# mechanical.net
KiCad netlist of a schematic drawn in Altium Designer
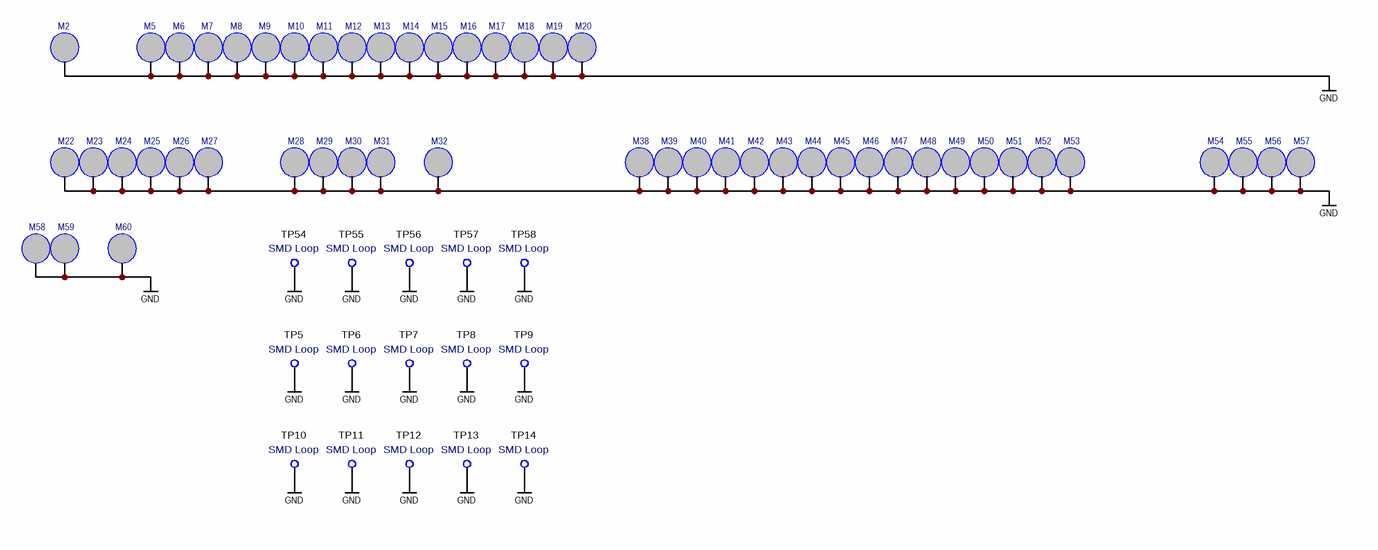
[diagram p0: mechanical.SchDoc]

(export (version "E")
  (design (tool "Eeschema 10.0.6"))
  (components
    (comp (ref "M2") (value "MOUNT") (footprint "MOUNTM3") (libsource (lib "generic") (part "MOUNT")))
    (comp (ref "M5") (value "MOUNT") (footprint "MOUNTM3") (libsource (lib "generic") (part "MOUNT")))
    (comp (ref "M6") (value "MOUNT") (footprint "MOUNTM3") (libsource (lib "generic") (part "MOUNT")))
    (comp (ref "M7") (value "MOUNT") (footprint "MOUNTM3") (libsource (lib "generic") (part "MOUNT")))
    (comp (ref "M8") (value "MOUNT") (footprint "MOUNTM3") (libsource (lib "generic") (part "MOUNT")))
    (comp (ref "M9") (value "MOUNT") (footprint "MOUNTM3") (libsource (lib "generic") (part "MOUNT")))
    (comp (ref "M10") (value "MOUNT") (footprint "MOUNTM3") (libsource (lib "generic") (part "MOUNT")))
    (comp (ref "M11") (value "MOUNT") (footprint "MOUNTM3") (libsource (lib "generic") (part "MOUNT")))
    (comp (ref "M12") (value "MOUNT") (footprint "MOUNTM3") (libsource (lib "generic") (part "MOUNT")))
    (comp (ref "M13") (value "MOUNT") (footprint "MOUNTM3") (libsource (lib "generic") (part "MOUNT")))
    (comp (ref "M14") (value "MOUNT") (footprint "MOUNTM3") (libsource (lib "generic") (part "MOUNT")))
    (comp (ref "M15") (value "MOUNT") (footprint "MOUNTM3") (libsource (lib "generic") (part "MOUNT")))
    (comp (ref "M16") (value "MOUNT") (footprint "MOUNTM3") (libsource (lib "generic") (part "MOUNT")))
    (comp (ref "M17") (value "MOUNT") (footprint "MOUNTM3") (libsource (lib "generic") (part "MOUNT")))
    (comp (ref "M18") (value "MOUNT") (footprint "MOUNTM3") (libsource (lib "generic") (part "MOUNT")))
    (comp (ref "M19") (value "MOUNT") (footprint "MOUNTM3") (libsource (lib "generic") (part "MOUNT")))
    (comp (ref "M20") (value "MOUNT") (footprint "MOUNTM3") (libsource (lib "generic") (part "MOUNT")))
    (comp (ref "M22") (value "MOUNT") (footprint "MOUNTM3") (libsource (lib "generic") (part "MOUNT")))
    (comp (ref "M23") (value "MOUNT") (footprint "MOUNTM3") (libsource (lib "generic") (part "MOUNT")))
    (comp (ref "M24") (value "MOUNT") (footprint "MOUNTM3") (libsource (lib "generic") (part "MOUNT")))
    (comp (ref "M25") (value "MOUNT") (footprint "MOUNTM3") (libsource (lib "generic") (part "MOUNT")))
    (comp (ref "M26") (value "MOUNT") (footprint "MOUNTM3") (libsource (lib "generic") (part "MOUNT")))
    (comp (ref "M27") (value "MOUNT") (footprint "MOUNTM3") (libsource (lib "generic") (part "MOUNT")))
    (comp (ref "M28") (value "MOUNT") (footprint "MOUNTM3") (libsource (lib "generic") (part "MOUNT")))
    (comp (ref "M29") (value "MOUNT") (footprint "MOUNTM3") (libsource (lib "generic") (part "MOUNT")))
    (comp (ref "M30") (value "MOUNT") (footprint "MOUNTM3") (libsource (lib "generic") (part "MOUNT")))
    (comp (ref "M31") (value "MOUNT") (footprint "MOUNTM3") (libsource (lib "generic") (part "MOUNT")))
    (comp (ref "M32") (value "MOUNT") (footprint "MOUNTM3") (libsource (lib "generic") (part "MOUNT")))
    (comp (ref "M38") (value "MOUNT") (footprint "MOUNTM3") (libsource (lib "generic") (part "MOUNT")))
    (comp (ref "M39") (value "MOUNT") (footprint "MOUNTM3") (libsource (lib "generic") (part "MOUNT")))
    (comp (ref "M40") (value "MOUNT") (footprint "MOUNTM3") (libsource (lib "generic") (part "MOUNT")))
    (comp (ref "M41") (value "MOUNT") (footprint "MOUNTM3") (libsource (lib "generic") (part "MOUNT")))
    (comp (ref "M42") (value "MOUNT") (footprint "MOUNTM3") (libsource (lib "generic") (part "MOUNT")))
    (comp (ref "M43") (value "MOUNT") (footprint "MOUNTM3") (libsource (lib "generic") (part "MOUNT")))
    (comp (ref "M44") (value "MOUNT") (footprint "MOUNTM3") (libsource (lib "generic") (part "MOUNT")))
    (comp (ref "M45") (value "MOUNT") (footprint "MOUNTM3") (libsource (lib "generic") (part "MOUNT")))
    (comp (ref "M46") (value "MOUNT") (footprint "MOUNTM3") (libsource (lib "generic") (part "MOUNT")))
    (comp (ref "M47") (value "MOUNT") (footprint "MOUNTM3") (libsource (lib "generic") (part "MOUNT")))
    (comp (ref "M48") (value "MOUNT") (footprint "MOUNTM3") (libsource (lib "generic") (part "MOUNT")))
    (comp (ref "M49") (value "MOUNT") (footprint "MOUNTM3") (libsource (lib "generic") (part "MOUNT")))
    (comp (ref "M50") (value "MOUNT") (footprint "MOUNTM3") (libsource (lib "generic") (part "MOUNT")))
    (comp (ref "M51") (value "MOUNT") (footprint "MOUNTM3") (libsource (lib "generic") (part "MOUNT")))
    (comp (ref "M52") (value "MOUNT") (footprint "MOUNTM3") (libsource (lib "generic") (part "MOUNT")))
    (comp (ref "M53") (value "MOUNT") (footprint "MOUNTM3") (libsource (lib "generic") (part "MOUNT")))
    (comp (ref "M54") (value "MOUNT") (footprint "MOUNTM3") (libsource (lib "generic") (part "MOUNT")))
    (comp (ref "M55") (value "MOUNT") (footprint "MOUNTM3") (libsource (lib "generic") (part "MOUNT")))
    (comp (ref "M56") (value "MOUNT") (footprint "MOUNTM3") (libsource (lib "generic") (part "MOUNT")))
    (comp (ref "M57") (value "MOUNT") (footprint "MOUNTM3") (libsource (lib "generic") (part "MOUNT")))
    (comp (ref "M58") (value "MOUNT") (footprint "MOUNTM3") (libsource (lib "generic") (part "MOUNT")))
    (comp (ref "M59") (value "MOUNT") (footprint "MOUNTM3") (libsource (lib "generic") (part "MOUNT")))
    (comp (ref "M60") (value "MOUNT") (footprint "MOUNTM3") (libsource (lib "generic") (part "MOUNT")))
    (comp (ref "TP5")
      (value "5015")
      (footprint "keystone:5015")
      (description "Test Point SMD")
      (fields (field (name "MANUFACTURER") "Keystone") (field (name "NOTES") "SMD Loop"))
      (libsource (lib "generic") (part "TEST_POINT_SMD_50"))
    )
    (comp (ref "TP6")
      (value "5015")
      (footprint "keystone:5015")
      (description "Test Point SMD")
      (fields (field (name "MANUFACTURER") "Keystone") (field (name "NOTES") "SMD Loop"))
      (libsource (lib "generic") (part "TEST_POINT_SMD_50"))
    )
    (comp (ref "TP7")
      (value "5015")
      (footprint "keystone:5015")
      (description "Test Point SMD")
      (fields (field (name "MANUFACTURER") "Keystone") (field (name "NOTES") "SMD Loop"))
      (libsource (lib "generic") (part "TEST_POINT_SMD_50"))
    )
    (comp (ref "TP8")
      (value "5015")
      (footprint "keystone:5015")
      (description "Test Point SMD")
      (fields (field (name "MANUFACTURER") "Keystone") (field (name "NOTES") "SMD Loop"))
      (libsource (lib "generic") (part "TEST_POINT_SMD_50"))
    )
    (comp (ref "TP9")
      (value "5015")
      (footprint "keystone:5015")
      (description "Test Point SMD")
      (fields (field (name "MANUFACTURER") "Keystone") (field (name "NOTES") "SMD Loop"))
      (libsource (lib "generic") (part "TEST_POINT_SMD_50"))
    )
    (comp (ref "TP10")
      (value "5015")
      (footprint "keystone:5015")
      (description "Test Point SMD")
      (fields (field (name "MANUFACTURER") "Keystone") (field (name "NOTES") "SMD Loop"))
      (libsource (lib "generic") (part "TEST_POINT_SMD_50"))
    )
    (comp (ref "TP11")
      (value "5015")
      (footprint "keystone:5015")
      (description "Test Point SMD")
      (fields (field (name "MANUFACTURER") "Keystone") (field (name "NOTES") "SMD Loop"))
      (libsource (lib "generic") (part "TEST_POINT_SMD_50"))
    )
    (comp (ref "TP12")
      (value "5015")
      (footprint "keystone:5015")
      (description "Test Point SMD")
      (fields (field (name "MANUFACTURER") "Keystone") (field (name "NOTES") "SMD Loop"))
      (libsource (lib "generic") (part "TEST_POINT_SMD_50"))
    )
    (comp (ref "TP13")
      (value "5015")
      (footprint "keystone:5015")
      (description "Test Point SMD")
      (fields (field (name "MANUFACTURER") "Keystone") (field (name "NOTES") "SMD Loop"))
      (libsource (lib "generic") (part "TEST_POINT_SMD_50"))
    )
    (comp (ref "TP14")
      (value "5015")
      (footprint "keystone:5015")
      (description "Test Point SMD")
      (fields (field (name "MANUFACTURER") "Keystone") (field (name "NOTES") "SMD Loop"))
      (libsource (lib "generic") (part "TEST_POINT_SMD_50"))
    )
    (comp (ref "TP54")
      (value "5015")
      (footprint "keystone:5015")
      (description "Test Point SMD")
      (fields (field (name "MANUFACTURER") "Keystone") (field (name "NOTES") "SMD Loop"))
      (libsource (lib "generic") (part "TEST_POINT_SMD_50"))
    )
    (comp (ref "TP55")
      (value "5015")
      (footprint "keystone:5015")
      (description "Test Point SMD")
      (fields (field (name "MANUFACTURER") "Keystone") (field (name "NOTES") "SMD Loop"))
      (libsource (lib "generic") (part "TEST_POINT_SMD_50"))
    )
    (comp (ref "TP56")
      (value "5015")
      (footprint "keystone:5015")
      (description "Test Point SMD")
      (fields (field (name "MANUFACTURER") "Keystone") (field (name "NOTES") "SMD Loop"))
      (libsource (lib "generic") (part "TEST_POINT_SMD_50"))
    )
    (comp (ref "TP57")
      (value "5015")
      (footprint "keystone:5015")
      (description "Test Point SMD")
      (fields (field (name "MANUFACTURER") "Keystone") (field (name "NOTES") "SMD Loop"))
      (libsource (lib "generic") (part "TEST_POINT_SMD_50"))
    )
    (comp (ref "TP58")
      (value "5015")
      (footprint "keystone:5015")
      (description "Test Point SMD")
      (fields (field (name "MANUFACTURER") "Keystone") (field (name "NOTES") "SMD Loop"))
      (libsource (lib "generic") (part "TEST_POINT_SMD_50"))
    )
  )
  (nets
    (net (code "1") (name "GND") (class "Default")
      (node (ref "M10") (pin "1") (pinfunction "MNT_1") (pintype "passive"))
      (node (ref "M11") (pin "1") (pinfunction "MNT_1") (pintype "passive"))
      (node (ref "M12") (pin "1") (pinfunction "MNT_1") (pintype "passive"))
      (node (ref "M13") (pin "1") (pinfunction "MNT_1") (pintype "passive"))
      (node (ref "M14") (pin "1") (pinfunction "MNT_1") (pintype "passive"))
      (node (ref "M15") (pin "1") (pinfunction "MNT_1") (pintype "passive"))
      (node (ref "M16") (pin "1") (pinfunction "MNT_1") (pintype "passive"))
      (node (ref "M17") (pin "1") (pinfunction "MNT_1") (pintype "passive"))
      (node (ref "M18") (pin "1") (pinfunction "MNT_1") (pintype "passive"))
      (node (ref "M19") (pin "1") (pinfunction "MNT_1") (pintype "passive"))
      (node (ref "M2") (pin "1") (pinfunction "MNT_1") (pintype "passive"))
      (node (ref "M20") (pin "1") (pinfunction "MNT_1") (pintype "passive"))
      (node (ref "M22") (pin "1") (pinfunction "MNT_1") (pintype "passive"))
      (node (ref "M23") (pin "1") (pinfunction "MNT_1") (pintype "passive"))
      (node (ref "M24") (pin "1") (pinfunction "MNT_1") (pintype "passive"))
      (node (ref "M25") (pin "1") (pinfunction "MNT_1") (pintype "passive"))
      (node (ref "M26") (pin "1") (pinfunction "MNT_1") (pintype "passive"))
      (node (ref "M27") (pin "1") (pinfunction "MNT_1") (pintype "passive"))
      (node (ref "M28") (pin "1") (pinfunction "MNT_1") (pintype "passive"))
      (node (ref "M29") (pin "1") (pinfunction "MNT_1") (pintype "passive"))
      (node (ref "M30") (pin "1") (pinfunction "MNT_1") (pintype "passive"))
      (node (ref "M31") (pin "1") (pinfunction "MNT_1") (pintype "passive"))
      (node (ref "M32") (pin "1") (pinfunction "MNT_1") (pintype "passive"))
      (node (ref "M38") (pin "1") (pinfunction "MNT_1") (pintype "passive"))
      (node (ref "M39") (pin "1") (pinfunction "MNT_1") (pintype "passive"))
      (node (ref "M40") (pin "1") (pinfunction "MNT_1") (pintype "passive"))
      (node (ref "M41") (pin "1") (pinfunction "MNT_1") (pintype "passive"))
      (node (ref "M42") (pin "1") (pinfunction "MNT_1") (pintype "passive"))
      (node (ref "M43") (pin "1") (pinfunction "MNT_1") (pintype "passive"))
      (node (ref "M44") (pin "1") (pinfunction "MNT_1") (pintype "passive"))
      (node (ref "M45") (pin "1") (pinfunction "MNT_1") (pintype "passive"))
      (node (ref "M46") (pin "1") (pinfunction "MNT_1") (pintype "passive"))
      (node (ref "M47") (pin "1") (pinfunction "MNT_1") (pintype "passive"))
      (node (ref "M48") (pin "1") (pinfunction "MNT_1") (pintype "passive"))
      (node (ref "M49") (pin "1") (pinfunction "MNT_1") (pintype "passive"))
      (node (ref "M5") (pin "1") (pinfunction "MNT_1") (pintype "passive"))
      (node (ref "M50") (pin "1") (pinfunction "MNT_1") (pintype "passive"))
      (node (ref "M51") (pin "1") (pinfunction "MNT_1") (pintype "passive"))
      (node (ref "M52") (pin "1") (pinfunction "MNT_1") (pintype "passive"))
      (node (ref "M53") (pin "1") (pinfunction "MNT_1") (pintype "passive"))
      (node (ref "M54") (pin "1") (pinfunction "MNT_1") (pintype "passive"))
      (node (ref "M55") (pin "1") (pinfunction "MNT_1") (pintype "passive"))
      (node (ref "M56") (pin "1") (pinfunction "MNT_1") (pintype "passive"))
      (node (ref "M57") (pin "1") (pinfunction "MNT_1") (pintype "passive"))
      (node (ref "M58") (pin "1") (pinfunction "MNT_1") (pintype "passive"))
      (node (ref "M59") (pin "1") (pinfunction "MNT_1") (pintype "passive"))
      (node (ref "M6") (pin "1") (pinfunction "MNT_1") (pintype "passive"))
      (node (ref "M60") (pin "1") (pinfunction "MNT_1") (pintype "passive"))
      (node (ref "M7") (pin "1") (pinfunction "MNT_1") (pintype "passive"))
      (node (ref "M8") (pin "1") (pinfunction "MNT_1") (pintype "passive"))
      (node (ref "M9") (pin "1") (pinfunction "MNT_1") (pintype "passive"))
      (node (ref "TP10") (pin "1") (pinfunction "1_1") (pintype "passive"))
      (node (ref "TP11") (pin "1") (pinfunction "1_1") (pintype "passive"))
      (node (ref "TP12") (pin "1") (pinfunction "1_1") (pintype "passive"))
      (node (ref "TP13") (pin "1") (pinfunction "1_1") (pintype "passive"))
      (node (ref "TP14") (pin "1") (pinfunction "1_1") (pintype "passive"))
      (node (ref "TP5") (pin "1") (pinfunction "1_1") (pintype "passive"))
      (node (ref "TP54") (pin "1") (pinfunction "1_1") (pintype "passive"))
      (node (ref "TP55") (pin "1") (pinfunction "1_1") (pintype "passive"))
      (node (ref "TP56") (pin "1") (pinfunction "1_1") (pintype "passive"))
      (node (ref "TP57") (pin "1") (pinfunction "1_1") (pintype "passive"))
      (node (ref "TP58") (pin "1") (pinfunction "1_1") (pintype "passive"))
      (node (ref "TP6") (pin "1") (pinfunction "1_1") (pintype "passive"))
      (node (ref "TP7") (pin "1") (pinfunction "1_1") (pintype "passive"))
      (node (ref "TP8") (pin "1") (pinfunction "1_1") (pintype "passive"))
      (node (ref "TP9") (pin "1") (pinfunction "1_1") (pintype "passive"))
    )
  )
)
